# CAN.net
KiCad netlist of a schematic drawn in Altium Designer
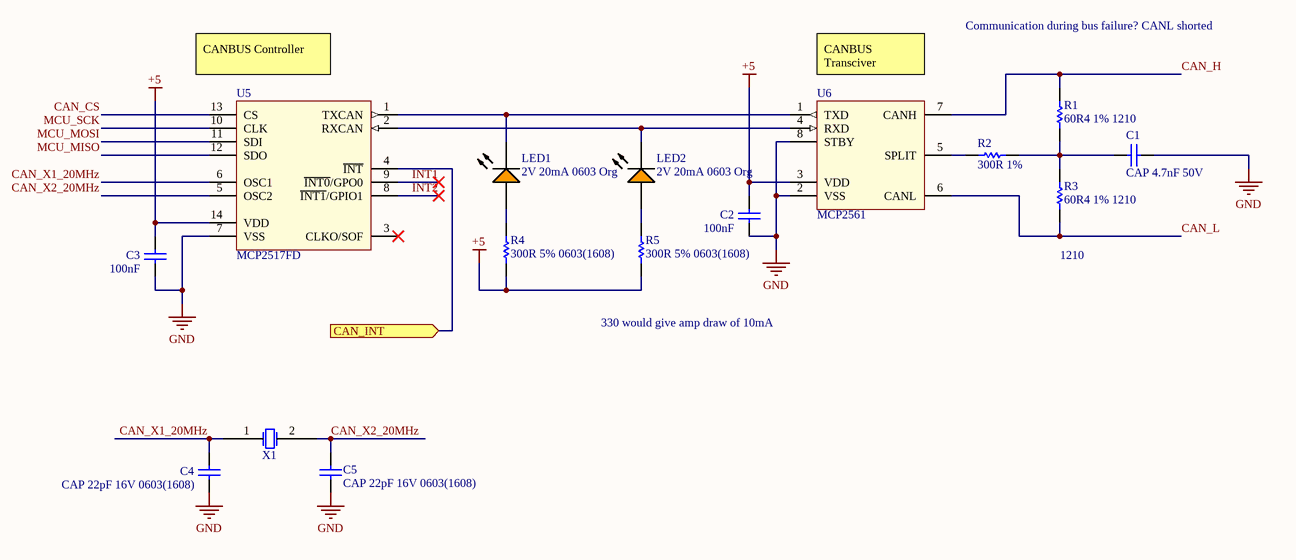
[diagram p0: CAN.SchDoc]

(export (version "E")
  (design (tool "Eeschema 10.0.6"))
  (components
    (comp (ref "C1")
      (value "CAP 4.7nF 50V")
      (footprint "CAPC0603(1608)100_L")
      (description "CAP 4.7nF 50V ±1% 0603 (1608 Metric) Thickness 1mm SMD")
      (fields (field (name "TOLERANCE") "Â±1%"))
      (libsource (lib "Altium Content Vault") (part "CAP"))
    )
    (comp (ref "C2")
      (value "100nF")
      (footprint "CAPC0603(1608)100_M")
      (description "CAP 100nF 16V ±5% 0603 (1608 Metric) Thickness 1mm SMD")
      (fields (field (name "TOLERANCE") "Â±5%"))
      (libsource (lib "Altium Content Vault") (part "CAP"))
    )
    (comp (ref "C3")
      (value "100nF")
      (footprint "CAPC0603(1608)100_M")
      (description "CAP 100nF 16V ±5% 0603 (1608 Metric) Thickness 1mm SMD")
      (fields (field (name "TOLERANCE") "Â±5%"))
      (libsource (lib "Altium Content Vault") (part "CAP"))
    )
    (comp (ref "C4")
      (value "CAP 22pF 16V 0603(1608)")
      (footprint "CAPC0603(1608)100_N")
      (description "CAP 22pF 16V ±5% 0603 (1608 Metric) Thickness 1mm SMD")
      (fields (field (name "TOLERANCE") "Â±5%"))
      (libsource (lib "Altium Content Vault") (part "CAP"))
    )
    (comp (ref "C5")
      (value "CAP 22pF 16V 0603(1608)")
      (footprint "CAPC0603(1608)100_N")
      (description "CAP 22pF 16V ±5% 0603 (1608 Metric) Thickness 1mm SMD")
      (fields (field (name "TOLERANCE") "Â±5%"))
      (libsource (lib "Altium Content Vault") (part "CAP"))
    )
    (comp (ref "LED1")
      (value "2V 20mA 0603 Org")
      (footprint "KING-LED0603-25-ORANGE_V")
      (description "LED, SMT, 0603(1608), 0.25mm Tthickness, Super Bright Orange")
      (fields (field (name "PARTNUMBER") "APG1608SEKC/T"))
      (libsource (lib "Altium Content Vault") (part "KING-LED_ORANGE_A1K2-2"))
    )
    (comp (ref "LED2")
      (value "2V 20mA 0603 Org")
      (footprint "KING-LED0603-25-ORANGE_V")
      (description "LED, SMT, 0603(1608), 0.25mm Tthickness, Super Bright Orange")
      (fields (field (name "PARTNUMBER") "APG1608SEKC/T"))
      (libsource (lib "Altium Content Vault") (part "KING-LED_ORANGE_A1K2-2"))
    )
    (comp (ref "R1")
      (value "60R4 1% 1210")
      (footprint "RESC1210(3225)_L")
      (description "60R4 0.5W 1% 1210 (3225 Metric)  SMD")
      (fields (field (name "TOLERANCE") "1 %") (field (name "POWER") "0.5 W"))
      (libsource (lib "Altium Content Vault") (part "RES"))
    )
    (comp (ref "R2")
      (value "300R 1%")
      (footprint "RESC0603(1608)_M")
      (description "300R 0.1W 1% 0603 (1608 Metric)  SMD")
      (fields (field (name "POWER") "0.1 W") (field (name "TOLERANCE") "1 %"))
      (libsource (lib "Altium Content Vault") (part "RES"))
    )
    (comp (ref "R3")
      (value "60R4 1% 1210")
      (footprint "RESC1210(3225)_L")
      (description "60R4 0.5W 1% 1210 (3225 Metric)  SMD")
      (fields (field (name "TOLERANCE") "1 %") (field (name "POWER") "0.5 W"))
      (libsource (lib "Altium Content Vault") (part "RES"))
    )
    (comp (ref "R4")
      (value "300R 5% 0603(1608)")
      (footprint "RESC0603(1608)_N")
      (description "300R 0.1W 5% 0603 (1608 Metric)  SMD")
      (fields (field (name "TOLERANCE") "5 %") (field (name "POWER") "0.1 W"))
      (libsource (lib "Altium Content Vault") (part "RES"))
    )
    (comp (ref "R5")
      (value "300R 5% 0603(1608)")
      (footprint "RESC0603(1608)_N")
      (description "300R 0.1W 5% 0603 (1608 Metric)  SMD")
      (fields (field (name "TOLERANCE") "5 %") (field (name "POWER") "0.1 W"))
      (libsource (lib "Altium Content Vault") (part "RES"))
    )
    (comp (ref "U5")
      (value "MCP2517FD")
      (footprint "MCP2517FD SOIC")
      (libsource (lib "QUTMS_CANLibrary") (part "MCP2517FD"))
    )
    (comp (ref "U6")
      (value "MCP2561")
      (footprint "MCP2561 SOIC")
      (libsource (lib "QUTMS_CANLibrary") (part "MCP2561"))
    )
    (comp (ref "X1")
      (value "Crystal 20MHz")
      (footprint "Crystal 20MHz")
      (libsource (lib "QUTMS_CrystalLibrary") (part "Crystal 20MHz"))
    )
  )
  (nets
    (net (code "1") (name "+5") (class "Default")
      (node (ref "C2") (pin "2") (pinfunction "2_2") (pintype "passive"))
      (node (ref "C3") (pin "2") (pinfunction "2_2") (pintype "passive"))
      (node (ref "R4") (pin "1") (pinfunction "1_1") (pintype "passive"))
      (node (ref "R5") (pin "1") (pinfunction "1_1") (pintype "passive"))
      (node (ref "U5") (pin "14") (pinfunction "VDD_14") (pintype "passive"))
      (node (ref "U6") (pin "3") (pinfunction "VDD_3") (pintype "passive"))
    )
    (net (code "2") (name "/CAN_CS") (class "Default")
      (node (ref "U5") (pin "13") (pinfunction "CS_13") (pintype "passive"))
    )
    (net (code "3") (name "/CAN_H") (class "Default")
      (node (ref "R1") (pin "2") (pinfunction "2_2") (pintype "passive"))
      (node (ref "U6") (pin "7") (pinfunction "CANH_7") (pintype "passive"))
    )
    (net (code "4") (name "/CAN_INT") (class "Default")
      (node (ref "U5") (pin "4") (pinfunction "~{INT}_4") (pintype "passive"))
    )
    (net (code "5") (name "/CAN_L") (class "Default")
      (node (ref "R3") (pin "1") (pinfunction "1_1") (pintype "passive"))
      (node (ref "U6") (pin "6") (pinfunction "CANL_6") (pintype "passive"))
    )
    (net (code "6") (name "/CAN_X1_20MHz") (class "Default")
      (node (ref "C4") (pin "2") (pinfunction "2_2") (pintype "passive"))
      (node (ref "U5") (pin "6") (pinfunction "OSC1_6") (pintype "passive"))
      (node (ref "X1") (pin "1") (pintype "passive"))
    )
    (net (code "7") (name "/CAN_X2_20MHz") (class "Default")
      (node (ref "C5") (pin "1") (pinfunction "1_1") (pintype "passive"))
      (node (ref "U5") (pin "5") (pinfunction "OSC2_5") (pintype "passive"))
      (node (ref "X1") (pin "2") (pintype "passive"))
    )
    (net (code "8") (name "/INT1") (class "Default")
      (node (ref "U5") (pin "9") (pinfunction "~{INT0}/GPO0_9") (pintype "passive+no_connect"))
    )
    (net (code "9") (name "/INT2") (class "Default")
      (node (ref "U5") (pin "8") (pinfunction "~{INT1}/GPIO1_8") (pintype "passive+no_connect"))
    )
    (net (code "10") (name "/MCU_MISO") (class "Default")
      (node (ref "U5") (pin "12") (pinfunction "SDO_12") (pintype "passive"))
    )
    (net (code "11") (name "/MCU_MOSI") (class "Default")
      (node (ref "U5") (pin "11") (pinfunction "SDI_11") (pintype "passive"))
    )
    (net (code "12") (name "/MCU_SCK") (class "Default")
      (node (ref "U5") (pin "10") (pinfunction "CLK_10") (pintype "passive"))
    )
    (net (code "13") (name "GND") (class "Default")
      (node (ref "C1") (pin "2") (pinfunction "2_2") (pintype "passive"))
      (node (ref "C2") (pin "1") (pinfunction "1_1") (pintype "passive"))
      (node (ref "C3") (pin "1") (pinfunction "1_1") (pintype "passive"))
      (node (ref "C4") (pin "1") (pinfunction "1_1") (pintype "passive"))
      (node (ref "C5") (pin "2") (pinfunction "2_2") (pintype "passive"))
      (node (ref "U5") (pin "7") (pinfunction "VSS_7") (pintype "passive"))
      (node (ref "U6") (pin "2") (pinfunction "VSS_2") (pintype "passive"))
      (node (ref "U6") (pin "8") (pinfunction "STBY_8") (pintype "passive"))
    )
    (net (code "14") (name "Net-(C1-Pad1)") (class "Default")
      (node (ref "C1") (pin "1") (pinfunction "1_1") (pintype "passive"))
      (node (ref "R1") (pin "1") (pinfunction "1_1") (pintype "passive"))
      (node (ref "R2") (pin "2") (pinfunction "2_2") (pintype "passive"))
      (node (ref "R3") (pin "2") (pinfunction "2_2") (pintype "passive"))
    )
    (net (code "15") (name "Net-(LED1-A)") (class "Default")
      (node (ref "LED1") (pin "1") (pinfunction "A_1") (pintype "passive"))
      (node (ref "R4") (pin "2") (pinfunction "2_2") (pintype "passive"))
    )
    (net (code "16") (name "Net-(LED1-K)") (class "Default")
      (node (ref "LED1") (pin "2") (pinfunction "K_2") (pintype "passive"))
      (node (ref "U5") (pin "1") (pinfunction "TXCAN_1") (pintype "output"))
      (node (ref "U6") (pin "1") (pinfunction "TXD_1") (pintype "output"))
    )
    (net (code "17") (name "Net-(LED2-A)") (class "Default")
      (node (ref "LED2") (pin "1") (pinfunction "A_1") (pintype "passive"))
      (node (ref "R5") (pin "2") (pinfunction "2_2") (pintype "passive"))
    )
    (net (code "18") (name "Net-(LED2-K)") (class "Default")
      (node (ref "LED2") (pin "2") (pinfunction "K_2") (pintype "passive"))
      (node (ref "U5") (pin "2") (pinfunction "RXCAN_2") (pintype "input"))
      (node (ref "U6") (pin "4") (pinfunction "RXD_4") (pintype "input"))
    )
    (net (code "19") (name "Net-(U6-SPLIT)") (class "Default")
      (node (ref "R2") (pin "1") (pinfunction "1_1") (pintype "passive"))
      (node (ref "U6") (pin "5") (pinfunction "SPLIT_5") (pintype "passive"))
    )
    (net (code "20") (name "unconnected-(U5-CLKO{slash}SOF-Pad3)") (class "Default")
      (node (ref "U5") (pin "3") (pinfunction "CLKO/SOF_3") (pintype "passive+no_connect"))
    )
  )
)
